# FM-Radio-Simple-Receiver-Dip4.net
KiCad netlist of a schematic drawn in EAGLE
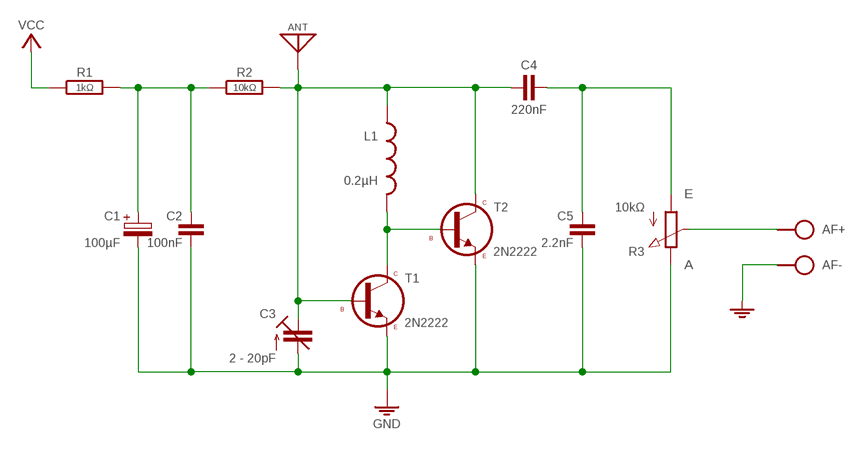
[diagram p0: schematic, sheet 1]

(export (version "E")
  (design (tool "Eeschema 10.0.6"))
  (components
    (comp (ref "AF")
      (value "SPAD+-+-")
      (footprint "eagle-import:SPAD+-")
      (libsource (lib "eagle-import") (part "SPAD+-+-"))
    )
    (comp (ref "ANT")
      (value "ANT")
      (footprint "eagle-import:SPAD")
      (libsource (lib "eagle-import") (part "ANT"))
    )
    (comp (ref "BAT")
      (value "VCC_GNDL")
      (footprint "eagle-import:SPAD-+")
      (libsource (lib "eagle-import") (part "VCC_GNDL"))
    )
    (comp (ref "C1")
      (value "100µF")
      (footprint "eagle-import:E2,5-5_V")
      (libsource (lib "eagle-import") (part "CPOLE2,5-5/V"))
    )
    (comp (ref "C2")
      (value "100nF")
      (footprint "eagle-import:C050-020X036_V")
      (libsource (lib "eagle-import") (part "C050-020X036/V"))
    )
    (comp (ref "C3")
      (value "2 - 20pF")
      (footprint "eagle-import:TRIM-2222-808")
      (libsource (lib "eagle-import") (part "C-TR-PH201272222-808-2PIND"))
    )
    (comp (ref "C4")
      (value "220nF")
      (footprint "eagle-import:C050-020X044")
      (libsource (lib "eagle-import") (part "C-H050-020X044"))
    )
    (comp (ref "C5")
      (value "2.2nF")
      (footprint "eagle-import:C050-020X036_V")
      (libsource (lib "eagle-import") (part "C050-020X036/V"))
    )
    (comp (ref "L1")
      (value "0.2µH")
      (footprint "eagle-import:L-10_10X")
      (libsource (lib "eagle-import") (part "L10/10X"))
    )
    (comp (ref "R1")
      (value "1kΩ")
      (footprint "eagle-import:0204_10")
      (libsource (lib "eagle-import") (part "R-H0204/10"))
    )
    (comp (ref "R2")
      (value "10kΩ")
      (footprint "eagle-import:0204_10")
      (libsource (lib "eagle-import") (part "R-H0204/10"))
    )
    (comp (ref "R3")
      (value "10kΩ")
      (footprint "eagle-import:CONN-3P")
      (libsource (lib "eagle-import") (part "POT-3P"))
    )
    (comp (ref "T1")
      (value "2N2222")
      (footprint "eagle-import:TO92")
      (libsource (lib "eagle-import") (part "2N2222"))
    )
    (comp (ref "T2")
      (value "2N2222")
      (footprint "eagle-import:TO92")
      (libsource (lib "eagle-import") (part "2N2222"))
    )
  )
  (nets
    (net (code "1") (name "GND") (class "Default")
      (node (ref "AF") (pin "1") (pinfunction "P$1_1") (pintype "passive"))
      (node (ref "BAT") (pin "1") (pinfunction "GND_1") (pintype "power_in"))
      (node (ref "C1") (pin "-") (pinfunction "-_-") (pintype "passive"))
      (node (ref "C2") (pin "2") (pinfunction "2_2") (pintype "passive"))
      (node (ref "C3") (pin "2") (pinfunction "A_2") (pintype "passive"))
      (node (ref "C5") (pin "2") (pinfunction "2_2") (pintype "passive"))
      (node (ref "R3") (pin "3") (pinfunction "E_3") (pintype "passive"))
      (node (ref "T1") (pin "1") (pinfunction "E_1") (pintype "passive"))
      (node (ref "T2") (pin "1") (pinfunction "E_1") (pintype "passive"))
    )
    (net (code "2") (name "Net-(AFA-P$1)") (class "Default")
      (node (ref "AF") (pin "2") (pinfunction "P$1_2") (pintype "passive"))
      (node (ref "R3") (pin "2") (pinfunction "S_2") (pintype "passive"))
    )
    (net (code "3") (name "Net-(BATA-VCC)") (class "Default")
      (node (ref "BAT") (pin "2") (pinfunction "VCC_2") (pintype "power_in"))
      (node (ref "R1") (pin "1") (pinfunction "1_1") (pintype "passive"))
    )
    (net (code "4") (name "Net-(C1-Pad+)") (class "Default")
      (node (ref "C1") (pin "+") (pinfunction "+_+") (pintype "passive"))
      (node (ref "C2") (pin "1") (pinfunction "1_1") (pintype "passive"))
      (node (ref "R1") (pin "2") (pinfunction "2_2") (pintype "passive"))
      (node (ref "R2") (pin "1") (pinfunction "1_1") (pintype "passive"))
    )
    (net (code "5") (name "Net-(C3-E)") (class "Default")
      (node (ref "ANT") (pin "1") (pinfunction "1_1") (pintype "output"))
      (node (ref "C3") (pin "3") (pinfunction "E_3") (pintype "passive"))
      (node (ref "C4") (pin "1") (pinfunction "1_1") (pintype "passive"))
      (node (ref "L1") (pin "P$1") (pinfunction "1_P$1") (pintype "passive"))
      (node (ref "R2") (pin "2") (pinfunction "2_2") (pintype "passive"))
      (node (ref "T1") (pin "2") (pinfunction "B_2") (pintype "passive"))
      (node (ref "T2") (pin "3") (pinfunction "C_3") (pintype "passive"))
    )
    (net (code "6") (name "Net-(L1-2)") (class "Default")
      (node (ref "L1") (pin "P$2") (pinfunction "2_P$2") (pintype "passive"))
      (node (ref "T1") (pin "3") (pinfunction "C_3") (pintype "passive"))
      (node (ref "T2") (pin "2") (pinfunction "B_2") (pintype "passive"))
    )
    (net (code "7") (name "Net-(R3-A)") (class "Default")
      (node (ref "C4") (pin "2") (pinfunction "2_2") (pintype "passive"))
      (node (ref "C5") (pin "1") (pinfunction "1_1") (pintype "passive"))
      (node (ref "R3") (pin "1") (pinfunction "A_1") (pintype "passive"))
    )
  )
)
